# module-encoders.net
KiCad netlist of a schematic drawn in EAGLE
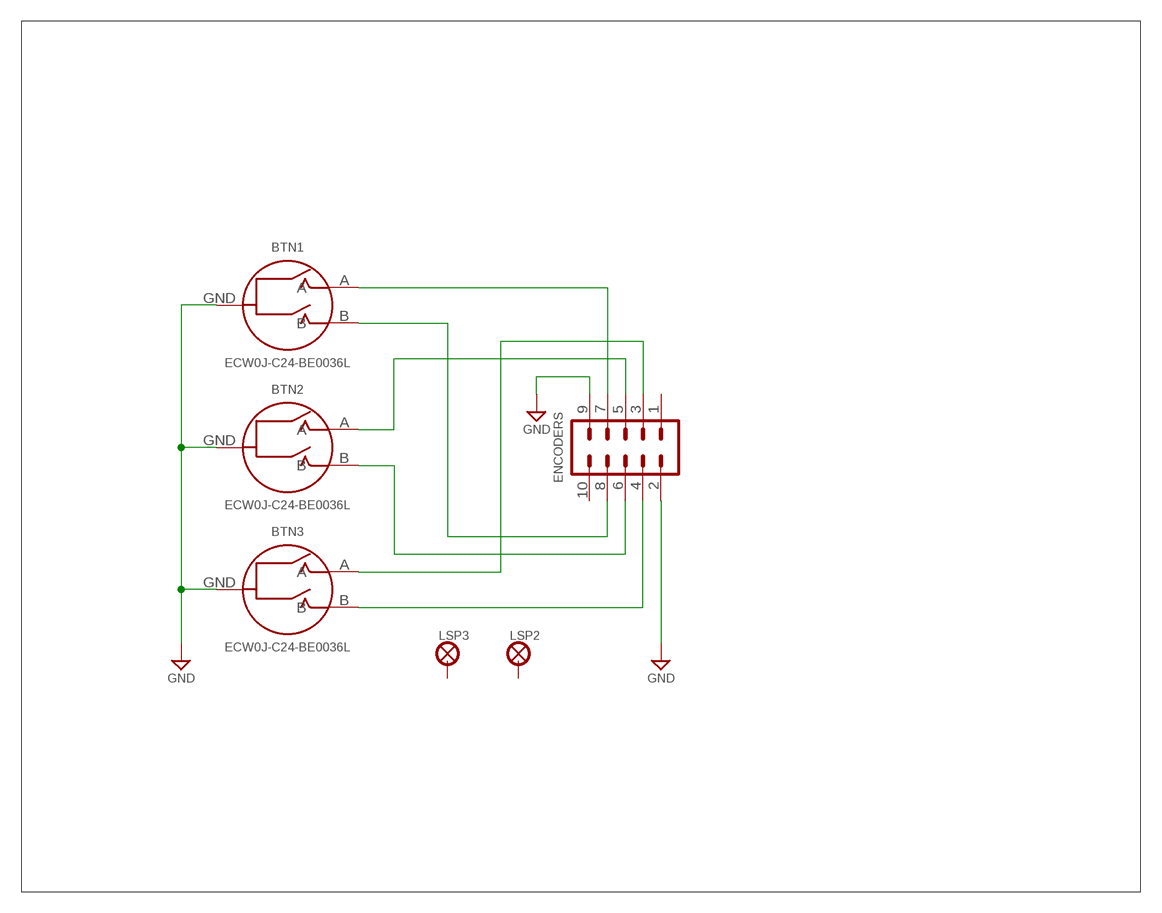
[diagram p0: schematic, sheet 1]

(export (version "E")
  (design (tool "Eeschema 10.0.6"))
  (components
    (comp (ref "BTN1")
      (value "ECW0J-C24-BE0036L")
      (footprint "eagle-import:ECW0J-C24")
      (libsource (lib "eagle-import") (part "ENCODER-ECW0J-C24"))
    )
    (comp (ref "BTN2")
      (value "ECW0J-C24-BE0036L")
      (footprint "eagle-import:ECW0J-C24")
      (libsource (lib "eagle-import") (part "ENCODER-ECW0J-C24"))
    )
    (comp (ref "BTN3")
      (value "ECW0J-C24-BE0036L")
      (footprint "eagle-import:ECW0J-C24")
      (libsource (lib "eagle-import") (part "ENCODER-ECW0J-C24"))
    )
    (comp (ref "ENCODERS")
      (value "MA05-2")
      (footprint "eagle-import:MA05-2")
      (libsource (lib "eagle-import") (part "MA05-2"))
    )
    (comp (ref "LSP2")
      (value "LSP27")
      (footprint "eagle-import:LSP27")
      (libsource (lib "eagle-import") (part "LSP27"))
    )
    (comp (ref "LSP3")
      (value "LSP27")
      (footprint "eagle-import:LSP27")
      (libsource (lib "eagle-import") (part "LSP27"))
    )
  )
  (nets
    (net (code "1") (name "GND") (class "Default")
      (node (ref "BTN1") (pin "GND") (pinfunction "GND_GND") (pintype "bidirectional"))
      (node (ref "BTN2") (pin "GND") (pinfunction "GND_GND") (pintype "bidirectional"))
      (node (ref "BTN3") (pin "GND") (pinfunction "GND_GND") (pintype "bidirectional"))
      (node (ref "ENCODERS") (pin "2") (pinfunction "2_2") (pintype "passive"))
      (node (ref "ENCODERS") (pin "9") (pinfunction "9_9") (pintype "passive"))
    )
    (net (code "2") (name "Net-(BTN1-PadA)") (class "Default")
      (node (ref "BTN1") (pin "A") (pinfunction "A_A") (pintype "bidirectional"))
      (node (ref "ENCODERS") (pin "7") (pinfunction "7_7") (pintype "passive"))
    )
    (net (code "3") (name "Net-(BTN1-PadB)") (class "Default")
      (node (ref "BTN1") (pin "B") (pinfunction "B_B") (pintype "bidirectional"))
      (node (ref "ENCODERS") (pin "8") (pinfunction "8_8") (pintype "passive"))
    )
    (net (code "4") (name "Net-(BTN2-PadA)") (class "Default")
      (node (ref "BTN2") (pin "A") (pinfunction "A_A") (pintype "bidirectional"))
      (node (ref "ENCODERS") (pin "5") (pinfunction "5_5") (pintype "passive"))
    )
    (net (code "5") (name "Net-(BTN2-PadB)") (class "Default")
      (node (ref "BTN2") (pin "B") (pinfunction "B_B") (pintype "bidirectional"))
      (node (ref "ENCODERS") (pin "6") (pinfunction "6_6") (pintype "passive"))
    )
    (net (code "6") (name "Net-(BTN3-PadA)") (class "Default")
      (node (ref "BTN3") (pin "A") (pinfunction "A_A") (pintype "bidirectional"))
      (node (ref "ENCODERS") (pin "3") (pinfunction "3_3") (pintype "passive"))
    )
    (net (code "7") (name "Net-(BTN3-PadB)") (class "Default")
      (node (ref "BTN3") (pin "B") (pinfunction "B_B") (pintype "bidirectional"))
      (node (ref "ENCODERS") (pin "4") (pinfunction "4_4") (pintype "passive"))
    )
    (net (code "8") (name "unconnected-(ENCODERS-Pad1)") (class "Default")
      (node (ref "ENCODERS") (pin "1") (pinfunction "1_1") (pintype "passive"))
    )
    (net (code "9") (name "unconnected-(ENCODERS-Pad10)") (class "Default")
      (node (ref "ENCODERS") (pin "10") (pinfunction "10_10") (pintype "passive"))
    )
    (net (code "10") (name "unconnected-(LSP2-PadMP)") (class "Default")
      (node (ref "LSP2") (pin "MP") (pinfunction "MP_MP") (pintype "passive"))
    )
    (net (code "11") (name "unconnected-(LSP3-PadMP)") (class "Default")
      (node (ref "LSP3") (pin "MP") (pinfunction "MP_MP") (pintype "passive"))
    )
  )
)
